# ECL_Fanout_X2.net
KiCad netlist of a schematic drawn in Altium Designer
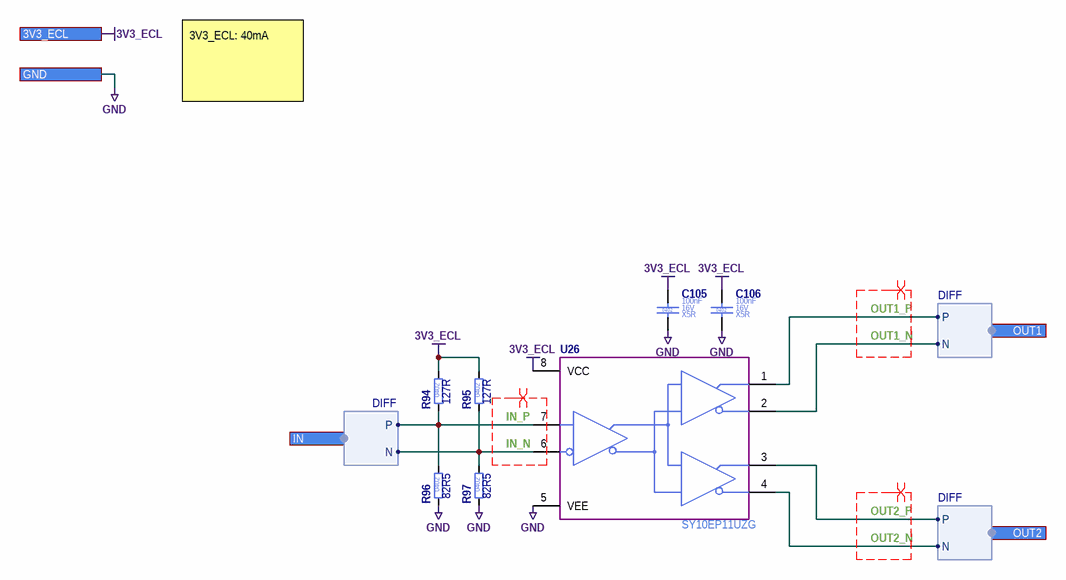
[diagram p0: ECL_Fanout_X2.SchDoc]

(export (version "E")
  (design (tool "Eeschema 10.0.6"))
  (components
    (comp (ref "C105")
      (value "C_100NF_16V_X5R_0402_10")
      (footprint "C_0402_1005")
      (description "Ceramic Capacitor")
      (fields
        (field (name "CASE/PACKAGE") "0402")
        (field (name "VOLTAGE RATING (DC)") "16V")
        (field (name "DIELECTRIC") "X5R")
        (field (name "CAPACITANCE") "100nF")
        (field (name "TOLERANCE") "10%")
        (field (name "MANUFACTURER PART NUMBER") "EMK105BJ104KV-F")
      )
      (libsource (lib "7Sigma") (part "C"))
    )
    (comp (ref "C106")
      (value "C_100NF_16V_X5R_0402_10")
      (footprint "C_0402_1005")
      (description "Ceramic Capacitor")
      (fields
        (field (name "CASE/PACKAGE") "0402")
        (field (name "VOLTAGE RATING (DC)") "16V")
        (field (name "DIELECTRIC") "X5R")
        (field (name "CAPACITANCE") "100nF")
        (field (name "TOLERANCE") "10%")
        (field (name "MANUFACTURER PART NUMBER") "EMK105BJ104KV-F")
      )
      (libsource (lib "7Sigma") (part "C"))
    )
    (comp (ref "R94")
      (value "R_127R_0402_1")
      (footprint "R_0402_1005")
      (description "Thick Film Resistor")
      (fields
        (field (name "RESISTANCE") "127R")
        (field (name "CASE/PACKAGE") "0402")
        (field (name "TOLERANCE") "1%")
        (field (name "MANUFACTURER") "Yageo")
      )
      (libsource (lib "7Sigma") (part "R"))
    )
    (comp (ref "R95")
      (value "R_127R_0402_1")
      (footprint "R_0402_1005")
      (description "Thick Film Resistor")
      (fields
        (field (name "RESISTANCE") "127R")
        (field (name "CASE/PACKAGE") "0402")
        (field (name "TOLERANCE") "1%")
        (field (name "MANUFACTURER") "Yageo")
      )
      (libsource (lib "7Sigma") (part "R"))
    )
    (comp (ref "R96")
      (value "R_82R5_0402_1")
      (footprint "R_0402_1005")
      (description "Thick Film Resistor")
      (fields
        (field (name "RESISTANCE") "82R5")
        (field (name "CASE/PACKAGE") "0402")
        (field (name "TOLERANCE") "1%")
        (field (name "MANUFACTURER") "Yageo")
      )
      (libsource (lib "7Sigma") (part "R"))
    )
    (comp (ref "R97")
      (value "R_82R5_0402_1")
      (footprint "R_0402_1005")
      (description "Thick Film Resistor")
      (fields
        (field (name "RESISTANCE") "82R5")
        (field (name "CASE/PACKAGE") "0402")
        (field (name "TOLERANCE") "1%")
        (field (name "MANUFACTURER") "Yageo")
      )
      (libsource (lib "7Sigma") (part "R"))
    )
    (comp (ref "U26")
      (value "SY10EP11UZG")
      (footprint "SOIC127P600X170-8N")
      (description "1:2 PECL Fanout Buffer")
      (fields
        (field (name "MANUFACTURER") "Microchip")
        (field (name "MANUFACTURER PART NUMBER") "SY10EP11UZG")
      )
      (libsource (lib "7Sigma") (part "SY10EP11U"))
    )
  )
  (nets
    (net (code "2") (name "/IN_N") (class "Default")
      (node (ref "R95") (pin "1") (pinfunction "1_1") (pintype "passive"))
      (node (ref "R97") (pin "2") (pinfunction "2_2") (pintype "passive"))
      (node (ref "U26") (pin "6") (pinfunction "D_6") (pintype "passive"))
    )
    (net (code "3") (name "/IN_P") (class "Default")
      (node (ref "R94") (pin "1") (pinfunction "1_1") (pintype "passive"))
      (node (ref "R96") (pin "2") (pinfunction "2_2") (pintype "passive"))
      (node (ref "U26") (pin "7") (pinfunction "D_7") (pintype "passive"))
    )
    (net (code "4") (name "/OUT1_N") (class "Default")
      (node (ref "U26") (pin "2") (pinfunction "/Q0_2") (pintype "passive"))
    )
    (net (code "5") (name "/OUT1_P") (class "Default")
      (node (ref "U26") (pin "1") (pinfunction "Q0_1") (pintype "passive"))
    )
    (net (code "6") (name "/OUT2_N") (class "Default")
      (node (ref "U26") (pin "4") (pinfunction "Q1_4") (pintype "passive"))
    )
    (net (code "7") (name "/OUT2_P") (class "Default")
      (node (ref "U26") (pin "3") (pinfunction "Q1_3") (pintype "passive"))
    )
    (net (code "9") (name "3V3_ECL") (class "Default")
      (node (ref "C105") (pin "1") (pinfunction "1_1") (pintype "passive"))
      (node (ref "C106") (pin "1") (pinfunction "1_1") (pintype "passive"))
      (node (ref "R94") (pin "2") (pinfunction "2_2") (pintype "passive"))
      (node (ref "R95") (pin "2") (pinfunction "2_2") (pintype "passive"))
      (node (ref "U26") (pin "8") (pinfunction "VCC_8") (pintype "passive"))
    )
    (net (code "10") (name "GND") (class "Default")
      (node (ref "C105") (pin "2") (pinfunction "2_2") (pintype "passive"))
      (node (ref "C106") (pin "2") (pinfunction "2_2") (pintype "passive"))
      (node (ref "R96") (pin "1") (pinfunction "1_1") (pintype "passive"))
      (node (ref "R97") (pin "1") (pinfunction "1_1") (pintype "passive"))
      (node (ref "U26") (pin "5") (pinfunction "VEE_5") (pintype "passive"))
    )
  )
)
